# OutputBlockConnector.net
KiCad netlist of a schematic drawn in Altium Designer
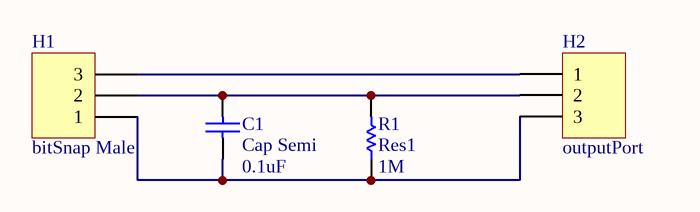
[diagram p0: OutputBlockConnector.SchDoc]

(export (version "E")
  (design (tool "Eeschema 10.0.6"))
  (components
    (comp (ref "C1")
      (value "Cap Semi")
      (footprint "CAPC3216L")
      (description "Capacitor (Semiconductor SIM Model)")
      (fields (field (name "ALTIUM_VALUE") "0.1uF") (field (name "PUBLISHER") "Altium Limited"))
      (libsource (lib "Miscellaneous Devices") (part "Cap Semi"))
    )
    (comp (ref "H1")
      (value "bitSnap Male")
      (footprint "HDR1X3")
      (description "Header, 3-Pin")
      (fields (field (name "PUBLISHER") "Altium Limited"))
      (libsource (lib "Miscellaneous Connectors") (part "Header 3"))
    )
    (comp (ref "H2")
      (value "outputPort")
      (footprint "HDR1X3")
      (description "Header, 3-Pin")
      (fields (field (name "PUBLISHER") "Altium Limited"))
      (libsource (lib "") (part "Header 3_1"))
    )
    (comp (ref "R1")
      (value "Res1")
      (footprint "AXIAL-0.3")
      (description "Resistor")
      (fields (field (name "ALTIUM_VALUE") "1M") (field (name "PUBLISHER") "Altium Limited"))
      (libsource (lib "Miscellaneous Devices") (part "Res1"))
    )
  )
  (nets
    (net (code "1") (name "Net-(C1-Pad1)") (class "Default")
      (node (ref "C1") (pin "1") (pinfunction "1_1") (pintype "passive"))
      (node (ref "H1") (pin "1") (pinfunction "1_1") (pintype "passive"))
      (node (ref "H2") (pin "3") (pinfunction "3_3") (pintype "passive"))
      (node (ref "R1") (pin "1") (pinfunction "1_1") (pintype "passive"))
    )
    (net (code "2") (name "Net-(C1-Pad2)") (class "Default")
      (node (ref "C1") (pin "2") (pinfunction "2_2") (pintype "passive"))
      (node (ref "H1") (pin "2") (pinfunction "2_2") (pintype "passive"))
      (node (ref "H2") (pin "2") (pinfunction "2_2") (pintype "passive"))
      (node (ref "R1") (pin "2") (pinfunction "2_2") (pintype "passive"))
    )
    (net (code "3") (name "Net-(H1-Pad3)") (class "Default")
      (node (ref "H1") (pin "3") (pinfunction "3_3") (pintype "passive"))
      (node (ref "H2") (pin "1") (pinfunction "1_1") (pintype "passive"))
    )
  )
)
